# 02-USER_IO_STATUS.net
KiCad netlist of a schematic drawn in Altium Designer
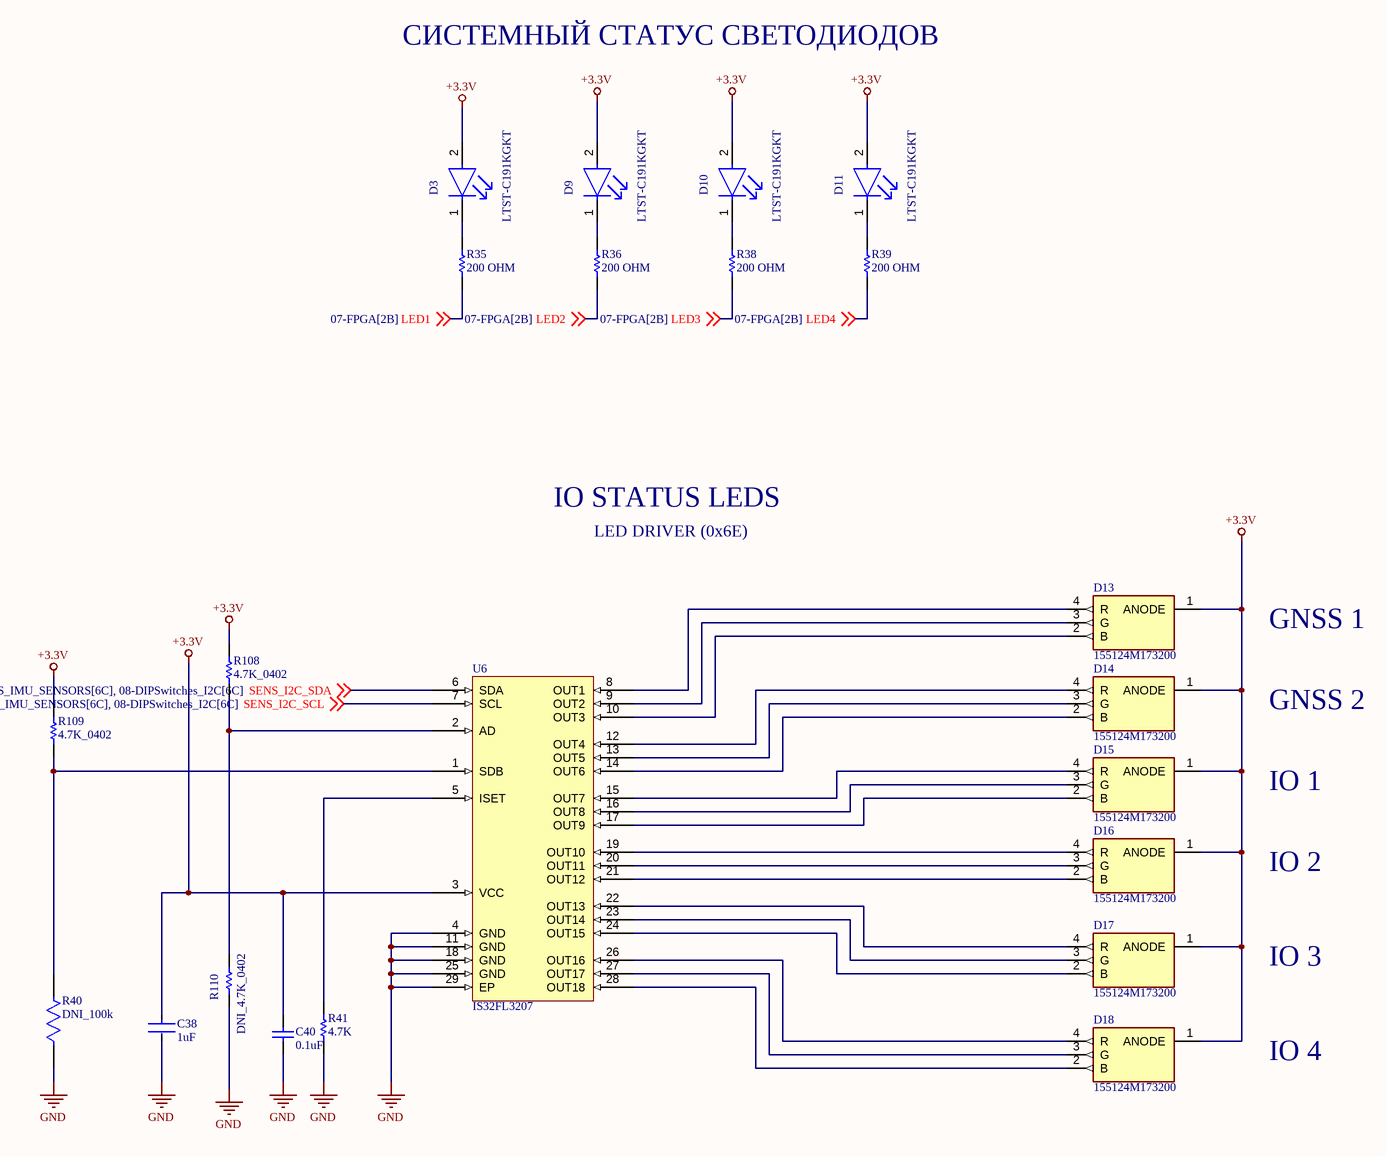
[diagram p0: 02-USER_IO_STATUS.SchDoc]

(export (version "E")
  (design (tool "Eeschema 10.0.6"))
  (components
    (comp (ref "C38")
      (value "1uF")
      (footprint "FP-C0603C105K3PACTU-MFG")
      (description "CAP CER 1UF 25V X5R 0603")
      (fields (field (name "VOLTAGE") "25V") (field (name "TOLERANCE") "10%"))
      (libsource (lib "Altium Content Vault") (part "e9c51b7dd13d4faca003ae77663ab08"))
    )
    (comp (ref "C40")
      (value "0.1uF")
      (footprint "CAPC1608X87X45ML20T05")
      (description "C0603X104K5RACAUTO")
      (fields (field (name "MANUFACTURER") "Kemet"))
      (libsource (lib "Altium Content Vault") (part "CAP"))
    )
    (comp (ref "D3")
      (value "LTST-C191KGKT")
      (footprint "FP-LTST-C191KGKT-MFG")
      (description "LED GREEN CLEAR SMD")
      (libsource (lib "Altium Content Vault") (part "8706943c75ba83719d021d2fdc84c58"))
    )
    (comp (ref "D9")
      (value "LTST-C191KGKT")
      (footprint "FP-LTST-C191KGKT-MFG")
      (description "LED GREEN CLEAR SMD")
      (libsource (lib "Altium Content Vault") (part "8706943c75ba83719d021d2fdc84c58"))
    )
    (comp (ref "D10")
      (value "LTST-C191KGKT")
      (footprint "FP-LTST-C191KGKT-MFG")
      (description "LED GREEN CLEAR SMD")
      (libsource (lib "Altium Content Vault") (part "8706943c75ba83719d021d2fdc84c58"))
    )
    (comp (ref "D11")
      (value "LTST-C191KGKT")
      (footprint "FP-LTST-C191KGKT-MFG")
      (description "LED GREEN CLEAR SMD")
      (libsource (lib "Altium Content Vault") (part "8706943c75ba83719d021d2fdc84c58"))
    )
    (comp (ref "D13")
      (value "155124M173200")
      (footprint "SamacSys:155124M173200")
      (description "LED (Multiple)")
      (fields (field (name "MOUSER PART NUMBER") "710-155124M173200"))
      (libsource (lib "SamacSys") (part "155124M173200"))
    )
    (comp (ref "D14")
      (value "155124M173200")
      (footprint "SamacSys:155124M173200")
      (description "LED (Multiple)")
      (fields (field (name "MOUSER PART NUMBER") "710-155124M173200"))
      (libsource (lib "SamacSys") (part "155124M173200"))
    )
    (comp (ref "D15")
      (value "155124M173200")
      (footprint "SamacSys:155124M173200")
      (description "LED (Multiple)")
      (fields (field (name "MOUSER PART NUMBER") "710-155124M173200"))
      (libsource (lib "SamacSys") (part "155124M173200"))
    )
    (comp (ref "D16")
      (value "155124M173200")
      (footprint "SamacSys:155124M173200")
      (description "LED (Multiple)")
      (fields (field (name "MOUSER PART NUMBER") "710-155124M173200"))
      (libsource (lib "SamacSys") (part "155124M173200"))
    )
    (comp (ref "D17")
      (value "155124M173200")
      (footprint "SamacSys:155124M173200")
      (description "LED (Multiple)")
      (fields (field (name "MOUSER PART NUMBER") "710-155124M173200"))
      (libsource (lib "SamacSys") (part "155124M173200"))
    )
    (comp (ref "D18")
      (value "155124M173200")
      (footprint "SamacSys:155124M173200")
      (description "LED (Multiple)")
      (fields (field (name "MOUSER PART NUMBER") "710-155124M173200"))
      (libsource (lib "SamacSys") (part "155124M173200"))
    )
    (comp (ref "R35")
      (value "200 OHM")
      (footprint "RESC1608X55X30NL15T15")
      (description "ERJ-3EKF2000V")
      (fields (field (name "MANUFACTURER") "Panasonic"))
      (libsource (lib "Altium Content Vault") (part "RES"))
    )
    (comp (ref "R36")
      (value "200 OHM")
      (footprint "RESC1608X55X30NL15T15")
      (description "ERJ-3EKF2000V")
      (fields (field (name "MANUFACTURER") "Panasonic"))
      (libsource (lib "Altium Content Vault") (part "RES"))
    )
    (comp (ref "R38")
      (value "200 OHM")
      (footprint "RESC1608X55X30NL15T15")
      (description "ERJ-3EKF2000V")
      (fields (field (name "MANUFACTURER") "Panasonic"))
      (libsource (lib "Altium Content Vault") (part "RES"))
    )
    (comp (ref "R39")
      (value "200 OHM")
      (footprint "RESC1608X55X30NL15T15")
      (description "ERJ-3EKF2000V")
      (fields (field (name "MANUFACTURER") "Panasonic"))
      (libsource (lib "Altium Content Vault") (part "RES"))
    )
    (comp (ref "R40")
      (value "DNI_100k")
      (footprint "FP-RC0603-0_55-MFG")
      (description "RES SMD 100K OHM 1% 1/10W 0603")
      (fields (field (name "TOLERANCE") "1%"))
      (libsource (lib "Altium Content Vault") (part "1029c3af85768c4190bb7ad29bc67b5"))
    )
    (comp (ref "R41")
      (value "4.7K")
      (footprint "RESC1608X55X30NL15T15")
      (fields (field (name "TOLERANCE") "5%"))
      (libsource (lib "Altium Content Vault") (part "RES-2"))
    )
    (comp (ref "R108")
      (value "4.7K_0402")
      (footprint "RESC1005X40X25LL05T05")
      (description "Chip Resistor, 4.7 KOhm, +/- 1%, 0.1 W, -55 to 155 degC, 0402 (1005 Metric), RoHS, Tape and Reel")
      (fields (field (name "TOLERANCE") "1%") (field (name "PARTNUMBER") "ERJ-2RKF4701X"))
      (libsource (lib "Altium Content Vault") (part "RES-2"))
    )
    (comp (ref "R109")
      (value "4.7K_0402")
      (footprint "RESC1005X40X25LL05T05")
      (description "Chip Resistor, 4.7 KOhm, +/- 1%, 0.1 W, -55 to 155 degC, 0402 (1005 Metric), RoHS, Tape and Reel")
      (fields (field (name "TOLERANCE") "1%") (field (name "PARTNUMBER") "ERJ-2RKF4701X"))
      (libsource (lib "Altium Content Vault") (part "RES-2"))
    )
    (comp (ref "R110")
      (value "DNI_4.7K_0402")
      (footprint "RESC1005X40X25LL05T05")
      (description "Chip Resistor, 4.7 KOhm, +/- 1%, 0.1 W, -55 to 155 degC, 0402 (1005 Metric), RoHS, Tape and Reel")
      (fields (field (name "TOLERANCE") "1%") (field (name "PARTNUMBER") "ERJ-2RKF4701X"))
      (libsource (lib "Altium Content Vault") (part "RES-2"))
    )
    (comp (ref "U6")
      (value "IS32FL3207")
      (footprint "IS32FL3207")
      (libsource (lib "IS32FL3207") (part "IS32FL3207"))
    )
  )
  (nets
    (net (code "1") (name "+3.3V") (class "Default")
      (node (ref "C38") (pin "1") (pinfunction "1_1") (pintype "passive"))
      (node (ref "C40") (pin "2") (pinfunction "2_2") (pintype "passive"))
      (node (ref "D10") (pin "2") (pinfunction "A_2") (pintype "passive"))
      (node (ref "D11") (pin "2") (pinfunction "A_2") (pintype "passive"))
      (node (ref "D13") (pin "1") (pinfunction "ANODE_1") (pintype "power_in"))
      (node (ref "D14") (pin "1") (pinfunction "ANODE_1") (pintype "power_in"))
      (node (ref "D15") (pin "1") (pinfunction "ANODE_1") (pintype "power_in"))
      (node (ref "D16") (pin "1") (pinfunction "ANODE_1") (pintype "power_in"))
      (node (ref "D17") (pin "1") (pinfunction "ANODE_1") (pintype "power_in"))
      (node (ref "D18") (pin "1") (pinfunction "ANODE_1") (pintype "power_in"))
      (node (ref "D3") (pin "2") (pinfunction "A_2") (pintype "passive"))
      (node (ref "D9") (pin "2") (pinfunction "A_2") (pintype "passive"))
      (node (ref "R108") (pin "1") (pinfunction "1_1") (pintype "passive"))
      (node (ref "R109") (pin "1") (pinfunction "1_1") (pintype "passive"))
      (node (ref "U6") (pin "3") (pinfunction "VCC_3") (pintype "input"))
    )
    (net (code "2") (name "GND") (class "Default")
      (node (ref "C38") (pin "2") (pinfunction "2_2") (pintype "passive"))
      (node (ref "C40") (pin "1") (pinfunction "1_1") (pintype "passive"))
      (node (ref "R110") (pin "2") (pinfunction "2_2") (pintype "passive"))
      (node (ref "R40") (pin "1") (pinfunction "1_1") (pintype "passive"))
      (node (ref "R41") (pin "1") (pinfunction "1_1") (pintype "passive"))
      (node (ref "U6") (pin "11") (pinfunction "GND_11") (pintype "input"))
      (node (ref "U6") (pin "18") (pinfunction "GND_18") (pintype "input"))
      (node (ref "U6") (pin "25") (pinfunction "GND_25") (pintype "input"))
      (node (ref "U6") (pin "29") (pinfunction "EP_29") (pintype "input"))
      (node (ref "U6") (pin "4") (pinfunction "GND_4") (pintype "input"))
    )
    (net (code "3") (name "LED1") (class "Default")
      (node (ref "R35") (pin "1") (pinfunction "1_1") (pintype "passive"))
    )
    (net (code "4") (name "LED2") (class "Default")
      (node (ref "R36") (pin "1") (pinfunction "1_1") (pintype "passive"))
    )
    (net (code "5") (name "LED3") (class "Default")
      (node (ref "R38") (pin "1") (pinfunction "1_1") (pintype "passive"))
    )
    (net (code "6") (name "LED4") (class "Default")
      (node (ref "R39") (pin "1") (pinfunction "1_1") (pintype "passive"))
    )
    (net (code "7") (name "Net-(D3-C)") (class "Default")
      (node (ref "D3") (pin "1") (pinfunction "C_1") (pintype "passive"))
      (node (ref "R35") (pin "2") (pinfunction "2_2") (pintype "passive"))
    )
    (net (code "8") (name "Net-(D9-C)") (class "Default")
      (node (ref "D9") (pin "1") (pinfunction "C_1") (pintype "passive"))
      (node (ref "R36") (pin "2") (pinfunction "2_2") (pintype "passive"))
    )
    (net (code "9") (name "Net-(D10-C)") (class "Default")
      (node (ref "D10") (pin "1") (pinfunction "C_1") (pintype "passive"))
      (node (ref "R38") (pin "2") (pinfunction "2_2") (pintype "passive"))
    )
    (net (code "10") (name "Net-(D11-C)") (class "Default")
      (node (ref "D11") (pin "1") (pinfunction "C_1") (pintype "passive"))
      (node (ref "R39") (pin "2") (pinfunction "2_2") (pintype "passive"))
    )
    (net (code "11") (name "Net-(D13-B)") (class "Default")
      (node (ref "D13") (pin "2") (pinfunction "B_2") (pintype "output"))
      (node (ref "U6") (pin "10") (pinfunction "OUT3_10") (pintype "input"))
    )
    (net (code "12") (name "Net-(D13-G)") (class "Default")
      (node (ref "D13") (pin "3") (pinfunction "G_3") (pintype "output"))
      (node (ref "U6") (pin "9") (pinfunction "OUT2_9") (pintype "input"))
    )
    (net (code "13") (name "Net-(D13-R)") (class "Default")
      (node (ref "D13") (pin "4") (pinfunction "R_4") (pintype "output"))
      (node (ref "U6") (pin "8") (pinfunction "OUT1_8") (pintype "input"))
    )
    (net (code "14") (name "Net-(D14-B)") (class "Default")
      (node (ref "D14") (pin "2") (pinfunction "B_2") (pintype "output"))
      (node (ref "U6") (pin "14") (pinfunction "OUT6_14") (pintype "input"))
    )
    (net (code "15") (name "Net-(D14-G)") (class "Default")
      (node (ref "D14") (pin "3") (pinfunction "G_3") (pintype "output"))
      (node (ref "U6") (pin "13") (pinfunction "OUT5_13") (pintype "input"))
    )
    (net (code "16") (name "Net-(D14-R)") (class "Default")
      (node (ref "D14") (pin "4") (pinfunction "R_4") (pintype "output"))
      (node (ref "U6") (pin "12") (pinfunction "OUT4_12") (pintype "input"))
    )
    (net (code "17") (name "Net-(D15-B)") (class "Default")
      (node (ref "D15") (pin "2") (pinfunction "B_2") (pintype "output"))
      (node (ref "U6") (pin "17") (pinfunction "OUT9_17") (pintype "input"))
    )
    (net (code "18") (name "Net-(D15-G)") (class "Default")
      (node (ref "D15") (pin "3") (pinfunction "G_3") (pintype "output"))
      (node (ref "U6") (pin "16") (pinfunction "OUT8_16") (pintype "input"))
    )
    (net (code "19") (name "Net-(D15-R)") (class "Default")
      (node (ref "D15") (pin "4") (pinfunction "R_4") (pintype "output"))
      (node (ref "U6") (pin "15") (pinfunction "OUT7_15") (pintype "input"))
    )
    (net (code "20") (name "Net-(D16-B)") (class "Default")
      (node (ref "D16") (pin "2") (pinfunction "B_2") (pintype "output"))
      (node (ref "U6") (pin "21") (pinfunction "OUT12_21") (pintype "input"))
    )
    (net (code "21") (name "Net-(D16-G)") (class "Default")
      (node (ref "D16") (pin "3") (pinfunction "G_3") (pintype "output"))
      (node (ref "U6") (pin "20") (pinfunction "OUT11_20") (pintype "input"))
    )
    (net (code "22") (name "Net-(D16-R)") (class "Default")
      (node (ref "D16") (pin "4") (pinfunction "R_4") (pintype "output"))
      (node (ref "U6") (pin "19") (pinfunction "OUT10_19") (pintype "input"))
    )
    (net (code "23") (name "Net-(D17-B)") (class "Default")
      (node (ref "D17") (pin "2") (pinfunction "B_2") (pintype "output"))
      (node (ref "U6") (pin "24") (pinfunction "OUT15_24") (pintype "input"))
    )
    (net (code "24") (name "Net-(D17-G)") (class "Default")
      (node (ref "D17") (pin "3") (pinfunction "G_3") (pintype "output"))
      (node (ref "U6") (pin "23") (pinfunction "OUT14_23") (pintype "input"))
    )
    (net (code "25") (name "Net-(D17-R)") (class "Default")
      (node (ref "D17") (pin "4") (pinfunction "R_4") (pintype "output"))
      (node (ref "U6") (pin "22") (pinfunction "OUT13_22") (pintype "input"))
    )
    (net (code "26") (name "Net-(D18-B)") (class "Default")
      (node (ref "D18") (pin "2") (pinfunction "B_2") (pintype "output"))
      (node (ref "U6") (pin "28") (pinfunction "OUT18_28") (pintype "input"))
    )
    (net (code "27") (name "Net-(D18-G)") (class "Default")
      (node (ref "D18") (pin "3") (pinfunction "G_3") (pintype "output"))
      (node (ref "U6") (pin "27") (pinfunction "OUT17_27") (pintype "input"))
    )
    (net (code "28") (name "Net-(D18-R)") (class "Default")
      (node (ref "D18") (pin "4") (pinfunction "R_4") (pintype "output"))
      (node (ref "U6") (pin "26") (pinfunction "OUT16_26") (pintype "input"))
    )
    (net (code "29") (name "Net-(U6-AD)") (class "Default")
      (node (ref "R108") (pin "2") (pinfunction "2_2") (pintype "passive"))
      (node (ref "R110") (pin "1") (pinfunction "1_1") (pintype "passive"))
      (node (ref "U6") (pin "2") (pinfunction "AD_2") (pintype "input"))
    )
    (net (code "30") (name "Net-(U6-ISET)") (class "Default")
      (node (ref "R41") (pin "2") (pinfunction "2_2") (pintype "passive"))
      (node (ref "U6") (pin "5") (pinfunction "ISET_5") (pintype "input"))
    )
    (net (code "31") (name "Net-(U6-SDB)") (class "Default")
      (node (ref "R109") (pin "2") (pinfunction "2_2") (pintype "passive"))
      (node (ref "R40") (pin "2") (pinfunction "2_2") (pintype "passive"))
      (node (ref "U6") (pin "1") (pinfunction "SDB_1") (pintype "input"))
    )
    (net (code "32") (name "SENS_I2C_SCL") (class "Default")
      (node (ref "U6") (pin "7") (pinfunction "SCL_7") (pintype "input"))
    )
    (net (code "33") (name "SENS_I2C_SDA") (class "Default")
      (node (ref "U6") (pin "6") (pinfunction "SDA_6") (pintype "input"))
    )
  )
)
